# TI_ADC_CURRENT.net
KiCad netlist of a schematic drawn in Altium Designer
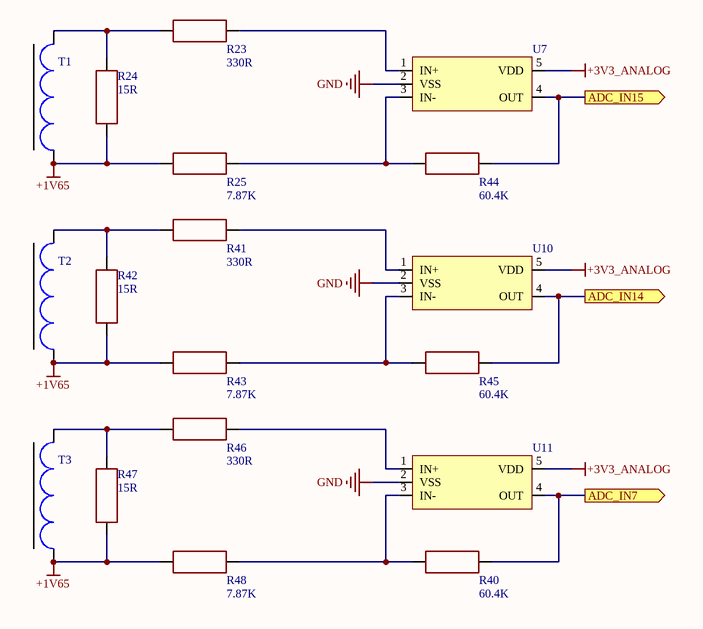
[diagram p0: TI_ADC_CURRENT.SchDoc]

(export (version "E")
  (design (tool "Eeschema 10.0.6"))
  (components
    (comp (ref "R23")
      (value "330R")
      (footprint "RES: 0603")
      (fields
        (field (name "POWER") "0.1W")
        (field (name "TOLERANCE") "±5%")
        (field (name "Comment") "Resistor_0603")
      )
      (libsource (lib "") (part "Resistor_0603_2"))
    )
    (comp (ref "R24")
      (value "15R")
      (footprint "RES: 0603")
      (fields
        (field (name "POWER") "0.1W")
        (field (name "TOLERANCE") "±5%")
        (field (name "Comment") "Resistor_0603")
      )
      (libsource (lib "resistor") (part "Resistor_0603"))
    )
    (comp (ref "R25")
      (value "7.87K")
      (footprint "RES: 0603")
      (fields
        (field (name "POWER") "0.1W")
        (field (name "TOLERANCE") "±5%")
        (field (name "Comment") "Resistor_0603")
      )
      (libsource (lib "") (part "Resistor_0603_2"))
    )
    (comp (ref "R40")
      (value "60.4K")
      (footprint "RES: 0603")
      (fields
        (field (name "POWER") "0.1W")
        (field (name "TOLERANCE") "±5%")
        (field (name "Comment") "Resistor_0603")
      )
      (libsource (lib "") (part "Resistor_0603_1"))
    )
    (comp (ref "R41")
      (value "330R")
      (footprint "RES: 0603")
      (fields
        (field (name "POWER") "0.1W")
        (field (name "TOLERANCE") "±5%")
        (field (name "Comment") "Resistor_0603")
      )
      (libsource (lib "resistor") (part "Resistor_0603"))
    )
    (comp (ref "R42")
      (value "15R")
      (footprint "RES: 0603")
      (fields
        (field (name "POWER") "0.1W")
        (field (name "TOLERANCE") "±5%")
        (field (name "Comment") "Resistor_0603")
      )
      (libsource (lib "") (part "Resistor_0603_1"))
    )
    (comp (ref "R43")
      (value "7.87K")
      (footprint "RES: 0603")
      (fields
        (field (name "POWER") "0.1W")
        (field (name "TOLERANCE") "±5%")
        (field (name "Comment") "Resistor_0603")
      )
      (libsource (lib "resistor") (part "Resistor_0603"))
    )
    (comp (ref "R44")
      (value "60.4K")
      (footprint "RES: 0603")
      (fields
        (field (name "POWER") "0.1W")
        (field (name "TOLERANCE") "±5%")
        (field (name "Comment") "Resistor_0603")
      )
      (libsource (lib "") (part "Resistor_0603_1"))
    )
    (comp (ref "R45")
      (value "60.4K")
      (footprint "RES: 0603")
      (fields
        (field (name "POWER") "0.1W")
        (field (name "TOLERANCE") "±5%")
        (field (name "Comment") "Resistor_0603")
      )
      (libsource (lib "") (part "Resistor_0603_1"))
    )
    (comp (ref "R46")
      (value "330R")
      (footprint "RES: 0603")
      (fields
        (field (name "POWER") "0.1W")
        (field (name "TOLERANCE") "±5%")
        (field (name "Comment") "Resistor_0603")
      )
      (libsource (lib "") (part "Resistor_0603_2"))
    )
    (comp (ref "R47")
      (value "15R")
      (footprint "RES: 0603")
      (fields
        (field (name "POWER") "0.1W")
        (field (name "TOLERANCE") "±5%")
        (field (name "Comment") "Resistor_0603")
      )
      (libsource (lib "resistor") (part "Resistor_0603"))
    )
    (comp (ref "R48")
      (value "7.87K")
      (footprint "RES: 0603")
      (fields
        (field (name "POWER") "0.1W")
        (field (name "TOLERANCE") "±5%")
        (field (name "Comment") "Resistor_0603")
      )
      (libsource (lib "") (part "Resistor_0603_2"))
    )
    (comp (ref "T1")
      (value "AC-1005")
      (footprint "AC-1005")
      (description "Current Transformer, primary current: 5A")
      (fields (field (name "MANUFACTURER") "Talema"))
      (libsource (lib "MY_INT_LIB") (part "AC-1005"))
    )
    (comp (ref "T2")
      (value "AC-1005")
      (footprint "AC-1005")
      (description "Current Transformer, primary current: 5A")
      (fields (field (name "MANUFACTURER") "Talema"))
      (libsource (lib "MY_INT_LIB") (part "AC-1005"))
    )
    (comp (ref "T3")
      (value "AC-1005")
      (footprint "AC-1005")
      (description "Current Transformer, primary current: 5A")
      (fields (field (name "MANUFACTURER") "Talema"))
      (libsource (lib "MY_INT_LIB") (part "AC-1005"))
    )
    (comp (ref "U7")
      (value "MCP6001U")
      (footprint "SOT-23-5")
      (description "1 MHz, Low-Power Op Amp")
      (fields (field (name "MANUFACTURER") "Microchip"))
      (libsource (lib "MY_INT_LIB") (part "MCP6001U"))
    )
    (comp (ref "U10")
      (value "MCP6001U")
      (footprint "SOT-23-5")
      (description "1 MHz, Low-Power Op Amp")
      (fields (field (name "MANUFACTURER") "Microchip"))
      (libsource (lib "MY_INT_LIB") (part "MCP6001U"))
    )
    (comp (ref "U11")
      (value "MCP6001U")
      (footprint "SOT-23-5")
      (description "1 MHz, Low-Power Op Amp")
      (fields (field (name "MANUFACTURER") "Microchip"))
      (libsource (lib "MY_INT_LIB") (part "MCP6001U"))
    )
  )
  (nets
    (net (code "1") (name "+1V65") (class "Default")
      (node (ref "R24") (pin "1") (pinfunction "1_1") (pintype "passive"))
      (node (ref "R25") (pin "1") (pinfunction "1_1") (pintype "passive"))
      (node (ref "R42") (pin "2") (pinfunction "2_2") (pintype "passive"))
      (node (ref "R43") (pin "1") (pinfunction "1_1") (pintype "passive"))
      (node (ref "R47") (pin "1") (pinfunction "1_1") (pintype "passive"))
      (node (ref "R48") (pin "1") (pinfunction "1_1") (pintype "passive"))
      (node (ref "T1") (pin "1") (pinfunction "1_1") (pintype "passive"))
      (node (ref "T2") (pin "1") (pinfunction "1_1") (pintype "passive"))
      (node (ref "T3") (pin "1") (pinfunction "1_1") (pintype "passive"))
    )
    (net (code "2") (name "+3V3_ANALOG") (class "Default")
      (node (ref "U10") (pin "5") (pinfunction "VDD_5") (pintype "power_in"))
      (node (ref "U11") (pin "5") (pinfunction "VDD_5") (pintype "power_in"))
      (node (ref "U7") (pin "5") (pinfunction "VDD_5") (pintype "power_in"))
    )
    (net (code "3") (name "/ADC_IN7") (class "Default")
      (node (ref "R40") (pin "1") (pinfunction "1_1") (pintype "passive"))
      (node (ref "U11") (pin "4") (pinfunction "OUT_4") (pintype "passive"))
    )
    (net (code "4") (name "/ADC_IN14") (class "Default")
      (node (ref "R45") (pin "1") (pinfunction "1_1") (pintype "passive"))
      (node (ref "U10") (pin "4") (pinfunction "OUT_4") (pintype "passive"))
    )
    (net (code "5") (name "/ADC_IN15") (class "Default")
      (node (ref "R44") (pin "1") (pinfunction "1_1") (pintype "passive"))
      (node (ref "U7") (pin "4") (pinfunction "OUT_4") (pintype "passive"))
    )
    (net (code "6") (name "GND") (class "Default")
      (node (ref "U10") (pin "2") (pinfunction "VSS_2") (pintype "power_in"))
      (node (ref "U11") (pin "2") (pinfunction "VSS_2") (pintype "power_in"))
      (node (ref "U7") (pin "2") (pinfunction "VSS_2") (pintype "power_in"))
    )
    (net (code "7") (name "Net-(R23-Pad1)") (class "Default")
      (node (ref "R23") (pin "1") (pinfunction "1_1") (pintype "passive"))
      (node (ref "R24") (pin "2") (pinfunction "2_2") (pintype "passive"))
      (node (ref "T1") (pin "2") (pinfunction "2_2") (pintype "passive"))
    )
    (net (code "8") (name "Net-(R41-Pad1)") (class "Default")
      (node (ref "R41") (pin "1") (pinfunction "1_1") (pintype "passive"))
      (node (ref "R42") (pin "1") (pinfunction "1_1") (pintype "passive"))
      (node (ref "T2") (pin "2") (pinfunction "2_2") (pintype "passive"))
    )
    (net (code "9") (name "Net-(R46-Pad1)") (class "Default")
      (node (ref "R46") (pin "1") (pinfunction "1_1") (pintype "passive"))
      (node (ref "R47") (pin "2") (pinfunction "2_2") (pintype "passive"))
      (node (ref "T3") (pin "2") (pinfunction "2_2") (pintype "passive"))
    )
    (net (code "10") (name "Net-(U7-IN+)") (class "Default")
      (node (ref "R23") (pin "2") (pinfunction "2_2") (pintype "passive"))
      (node (ref "U7") (pin "1") (pinfunction "IN+_1") (pintype "passive"))
    )
    (net (code "11") (name "Net-(U7-IN-)") (class "Default")
      (node (ref "R25") (pin "2") (pinfunction "2_2") (pintype "passive"))
      (node (ref "R44") (pin "2") (pinfunction "2_2") (pintype "passive"))
      (node (ref "U7") (pin "3") (pinfunction "IN-_3") (pintype "passive"))
    )
    (net (code "12") (name "Net-(U10-IN+)") (class "Default")
      (node (ref "R41") (pin "2") (pinfunction "2_2") (pintype "passive"))
      (node (ref "U10") (pin "1") (pinfunction "IN+_1") (pintype "passive"))
    )
    (net (code "13") (name "Net-(U10-IN-)") (class "Default")
      (node (ref "R43") (pin "2") (pinfunction "2_2") (pintype "passive"))
      (node (ref "R45") (pin "2") (pinfunction "2_2") (pintype "passive"))
      (node (ref "U10") (pin "3") (pinfunction "IN-_3") (pintype "passive"))
    )
    (net (code "14") (name "Net-(U11-IN+)") (class "Default")
      (node (ref "R46") (pin "2") (pinfunction "2_2") (pintype "passive"))
      (node (ref "U11") (pin "1") (pinfunction "IN+_1") (pintype "passive"))
    )
    (net (code "15") (name "Net-(U11-IN-)") (class "Default")
      (node (ref "R40") (pin "2") (pinfunction "2_2") (pintype "passive"))
      (node (ref "R48") (pin "2") (pinfunction "2_2") (pintype "passive"))
      (node (ref "U11") (pin "3") (pinfunction "IN-_3") (pintype "passive"))
    )
  )
)
